# EddieBoardA1.net
KiCad netlist of a schematic drawn in EAGLE
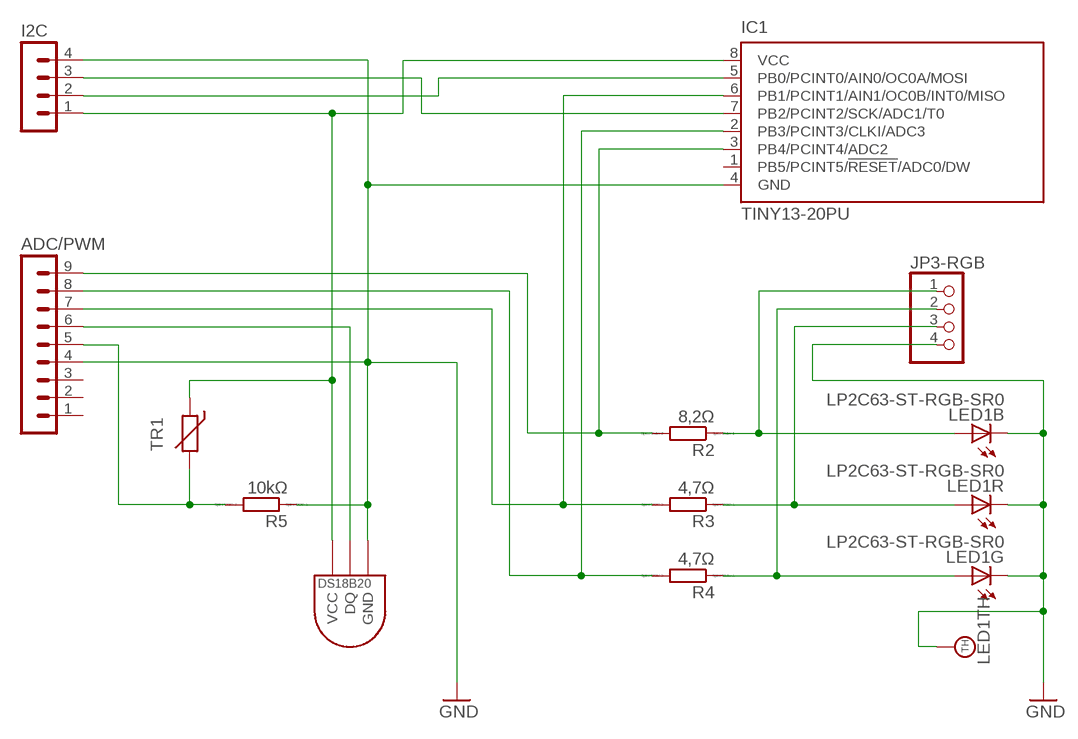
[diagram p0: schematic, sheet 1]

(export (version "E")
  (design (tool "Eeschema 10.0.6"))
  (components
    (comp (ref "ADC/PWM")
      (value "MA09-1")
      (footprint "eagle-import:MA09-1")
      (libsource (lib "eagle-import") (part "MA09-1"))
    )
    (comp (ref "I2C")
      (value "MA04-1")
      (footprint "eagle-import:MA04-1")
      (libsource (lib "eagle-import") (part "MA04-1"))
    )
    (comp (ref "IC1")
      (value "TINY13-20PU")
      (footprint "eagle-import:DIL08")
      (fields (field (name "MPN") "ATTINY13-20PU"))
      (libsource (lib "eagle-import") (part "TINY13PU-20"))
    )
    (comp (ref "JP3-RGB")
      (value "PINHD-1X4")
      (footprint "eagle-import:1X04")
      (libsource (lib "eagle-import") (part "PINHD-1X4"))
    )
    (comp (ref "LED1")
      (value "LP2C63-ST-RGB-SR0")
      (footprint "eagle-import:LP2C63-ST-RGB-SR0")
      (libsource (lib "eagle-import") (part "LP2C63-ST-RGB-SR0"))
    )
    (comp (ref "R2")
      (value "8,2Ω")
      (footprint "eagle-import:0204_7")
      (libsource (lib "eagle-import") (part "R0204/7"))
    )
    (comp (ref "R3")
      (value "4,7Ω")
      (footprint "eagle-import:0204_7")
      (libsource (lib "eagle-import") (part "R0204/7"))
    )
    (comp (ref "R4")
      (value "4,7Ω")
      (footprint "eagle-import:0204_7")
      (libsource (lib "eagle-import") (part "R0204/7"))
    )
    (comp (ref "R5")
      (value "10kΩ")
      (footprint "eagle-import:0204_7")
      (libsource (lib "eagle-import") (part "R0204/7"))
    )
    (comp (ref "TR1")
      (value "THERMISTOR_R-5")
      (footprint "eagle-import:R-5")
      (libsource (lib "eagle-import") (part "THERMISTOR_R-5"))
    )
    (comp (ref "U$1")
      (value "DS1820TO92")
      (footprint "eagle-import:DS1820")
      (libsource (lib "eagle-import") (part "DS1820TO92"))
    )
  )
  (nets
    (net (code "1") (name "GND") (class "Default")
      (node (ref "ADC/PWM") (pin "4") (pinfunction "4_4") (pintype "passive"))
      (node (ref "I2C") (pin "4") (pinfunction "4_4") (pintype "passive"))
      (node (ref "IC1") (pin "4") (pinfunction "GND_4") (pintype "power_in"))
      (node (ref "JP3-RGB") (pin "4") (pinfunction "4_4") (pintype "passive"))
      (node (ref "LED1") (pin "4") (pinfunction "C_4") (pintype "passive"))
      (node (ref "LED1") (pin "5") (pinfunction "C_5") (pintype "passive"))
      (node (ref "LED1") (pin "6") (pinfunction "C_6") (pintype "passive"))
      (node (ref "LED1") (pin "TH") (pinfunction "TH_TH") (pintype "passive"))
      (node (ref "R5") (pin "1") (pinfunction "1_1") (pintype "passive"))
      (node (ref "U$1") (pin "GND") (pinfunction "GND_GND") (pintype "power_in"))
    )
    (net (code "2") (name "Net-(ADC/PWM-Pad5)") (class "Default")
      (node (ref "ADC/PWM") (pin "5") (pinfunction "5_5") (pintype "passive"))
      (node (ref "R5") (pin "2") (pinfunction "2_2") (pintype "passive"))
      (node (ref "TR1") (pin "2") (pinfunction "2_2") (pintype "passive"))
    )
    (net (code "3") (name "Net-(ADC/PWM-Pad6)") (class "Default")
      (node (ref "ADC/PWM") (pin "6") (pinfunction "6_6") (pintype "passive"))
      (node (ref "U$1") (pin "DQ") (pinfunction "DQ_DQ") (pintype "bidirectional"))
    )
    (net (code "4") (name "Net-(IC1-PB0{slash}PCINT0{slash}AIN0{slash}OC0A{slash}MOSI)") (class "Default")
      (node (ref "I2C") (pin "2") (pinfunction "2_2") (pintype "passive"))
      (node (ref "IC1") (pin "5") (pinfunction "PB0/PCINT0/AIN0/OC0A/MOSI_5") (pintype "bidirectional"))
    )
    (net (code "5") (name "Net-(IC1-PB1{slash}PCINT1{slash}AIN1{slash}OC0B{slash}INT0{slash}MISO)") (class "Default")
      (node (ref "ADC/PWM") (pin "7") (pinfunction "7_7") (pintype "passive"))
      (node (ref "IC1") (pin "6") (pinfunction "PB1/PCINT1/AIN1/OC0B/INT0/MISO_6") (pintype "bidirectional"))
      (node (ref "R3") (pin "2") (pinfunction "2_2") (pintype "passive"))
    )
    (net (code "6") (name "Net-(IC1-PB2{slash}PCINT2{slash}SCK{slash}ADC1{slash}T0)") (class "Default")
      (node (ref "I2C") (pin "3") (pinfunction "3_3") (pintype "passive"))
      (node (ref "IC1") (pin "7") (pinfunction "PB2/PCINT2/SCK/ADC1/T0_7") (pintype "bidirectional"))
    )
    (net (code "7") (name "Net-(IC1-PB3{slash}PCINT3{slash}CLKI{slash}ADC3)") (class "Default")
      (node (ref "ADC/PWM") (pin "8") (pinfunction "8_8") (pintype "passive"))
      (node (ref "IC1") (pin "2") (pinfunction "PB3/PCINT3/CLKI/ADC3_2") (pintype "bidirectional"))
      (node (ref "R4") (pin "2") (pinfunction "2_2") (pintype "passive"))
    )
    (net (code "8") (name "Net-(IC1-PB4{slash}PCINT4{slash}ADC2)") (class "Default")
      (node (ref "ADC/PWM") (pin "9") (pinfunction "9_9") (pintype "passive"))
      (node (ref "IC1") (pin "3") (pinfunction "PB4/PCINT4/ADC2_3") (pintype "bidirectional"))
      (node (ref "R2") (pin "2") (pinfunction "2_2") (pintype "passive"))
    )
    (net (code "9") (name "Net-(IC1-VCC)") (class "Default")
      (node (ref "I2C") (pin "1") (pinfunction "1_1") (pintype "passive"))
      (node (ref "IC1") (pin "8") (pinfunction "VCC_8") (pintype "power_in"))
      (node (ref "TR1") (pin "1") (pinfunction "1_1") (pintype "passive"))
      (node (ref "U$1") (pin "VDD") (pinfunction "VCC_VDD") (pintype "power_in"))
    )
    (net (code "10") (name "Net-(LED1A-A)") (class "Default")
      (node (ref "JP3-RGB") (pin "1") (pinfunction "1_1") (pintype "passive"))
      (node (ref "LED1") (pin "3") (pinfunction "A_3") (pintype "passive"))
      (node (ref "R2") (pin "1") (pinfunction "1_1") (pintype "passive"))
    )
    (net (code "11") (name "Net-(LED1B-A)") (class "Default")
      (node (ref "JP3-RGB") (pin "2") (pinfunction "2_2") (pintype "passive"))
      (node (ref "LED1") (pin "1") (pinfunction "A_1") (pintype "passive"))
      (node (ref "R4") (pin "1") (pinfunction "1_1") (pintype "passive"))
    )
    (net (code "12") (name "Net-(LED1C-A)") (class "Default")
      (node (ref "JP3-RGB") (pin "3") (pinfunction "3_3") (pintype "passive"))
      (node (ref "LED1") (pin "2") (pinfunction "A_2") (pintype "passive"))
      (node (ref "R3") (pin "1") (pinfunction "1_1") (pintype "passive"))
    )
    (net (code "13") (name "unconnected-(ADC/PWM-Pad1)") (class "Default")
      (node (ref "ADC/PWM") (pin "1") (pinfunction "1_1") (pintype "passive"))
    )
    (net (code "14") (name "unconnected-(ADC/PWM-Pad2)") (class "Default")
      (node (ref "ADC/PWM") (pin "2") (pinfunction "2_2") (pintype "passive"))
    )
    (net (code "15") (name "unconnected-(ADC/PWM-Pad3)") (class "Default")
      (node (ref "ADC/PWM") (pin "3") (pinfunction "3_3") (pintype "passive"))
    )
    (net (code "16") (name "unconnected-(IC1-PB5{slash}PCINT5{slash}~{RESET}{slash}ADC0{slash}DW-Pad1)") (class "Default")
      (node (ref "IC1") (pin "1") (pinfunction "PB5/PCINT5/~{RESET}/ADC0/DW_1") (pintype "bidirectional"))
    )
  )
)
